# LPmini-Prototype_1_2.net
KiCad netlist of a schematic drawn in EAGLE
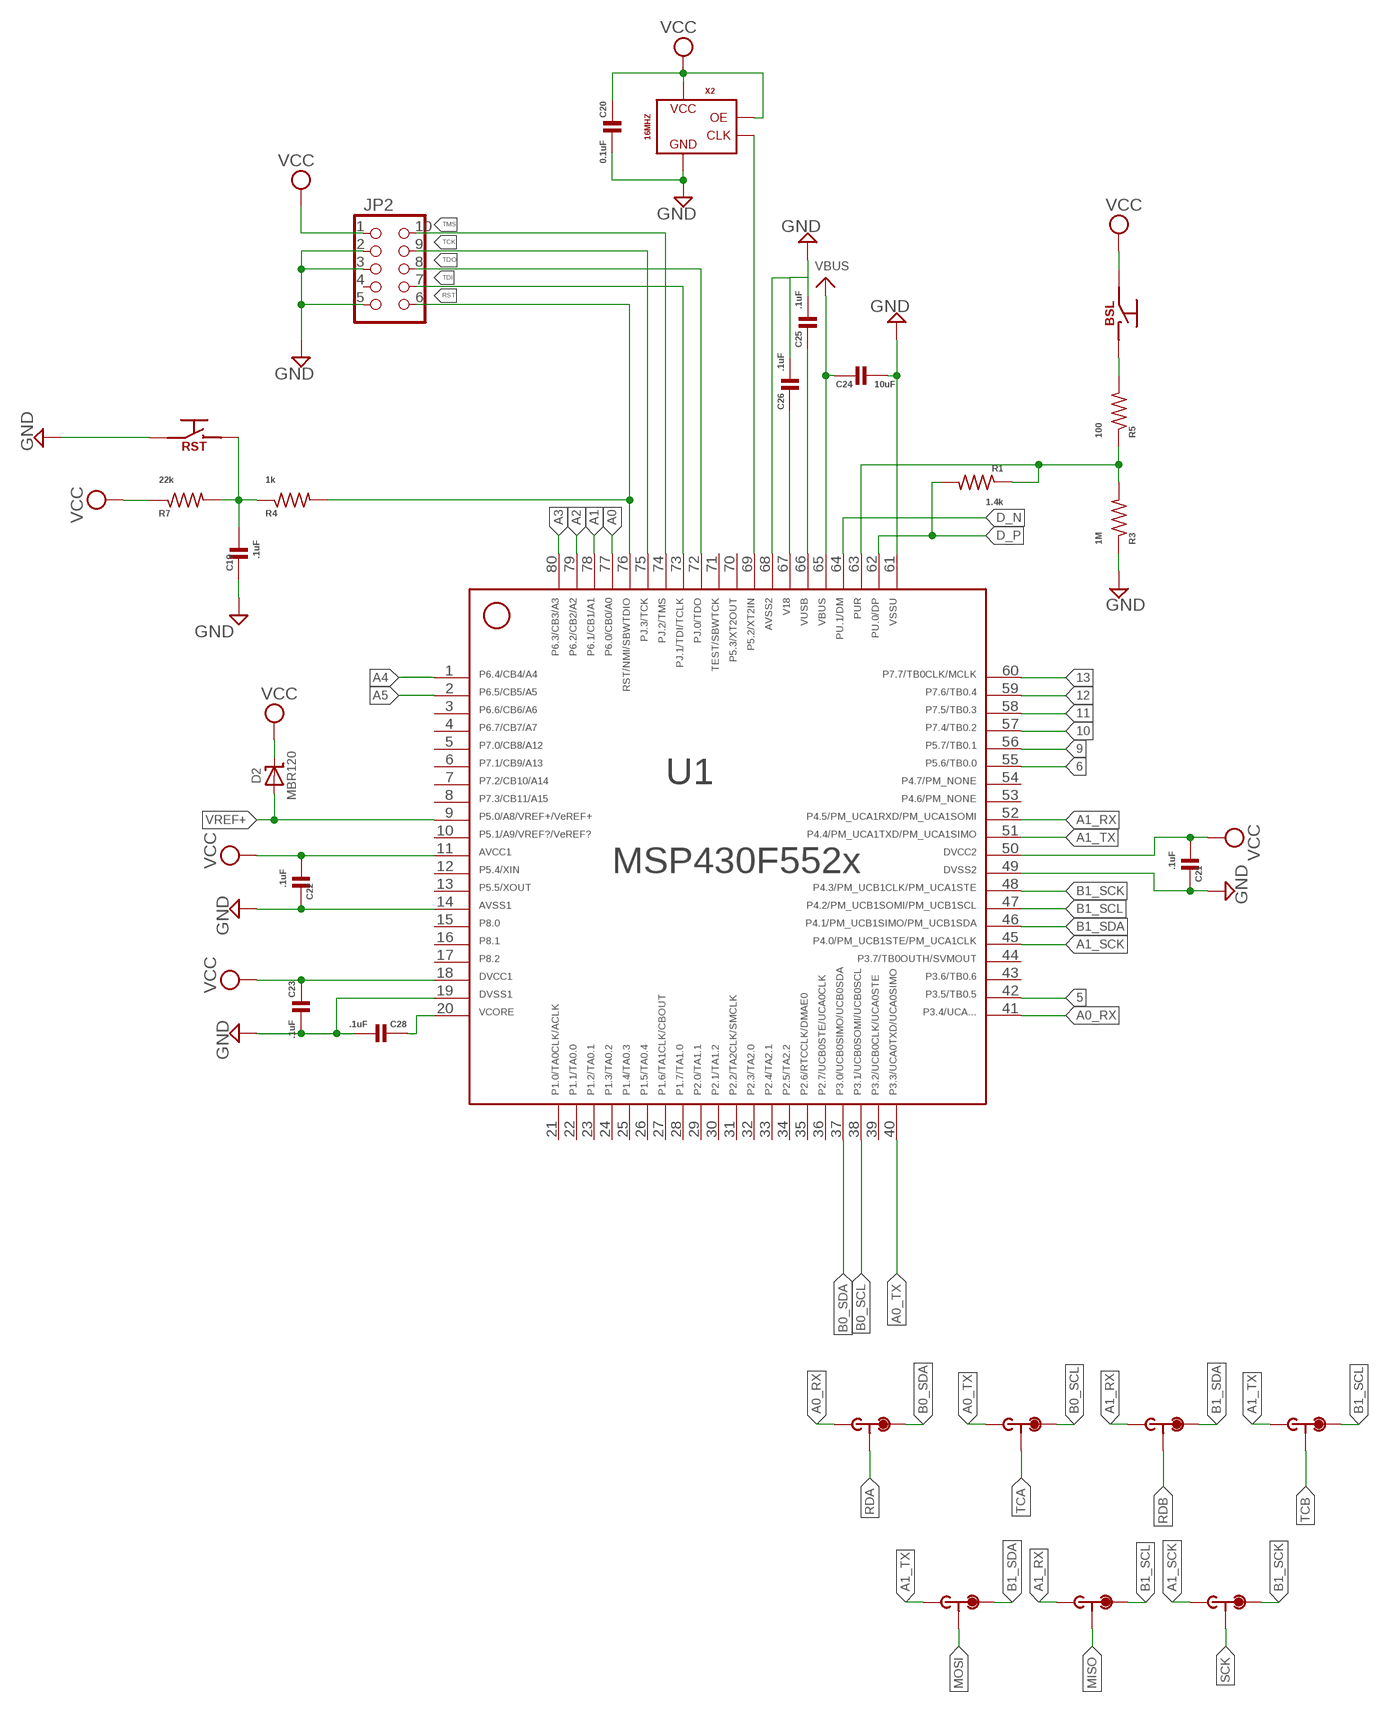
[diagram p0: schematic, sheet 1, part 1 of 2]
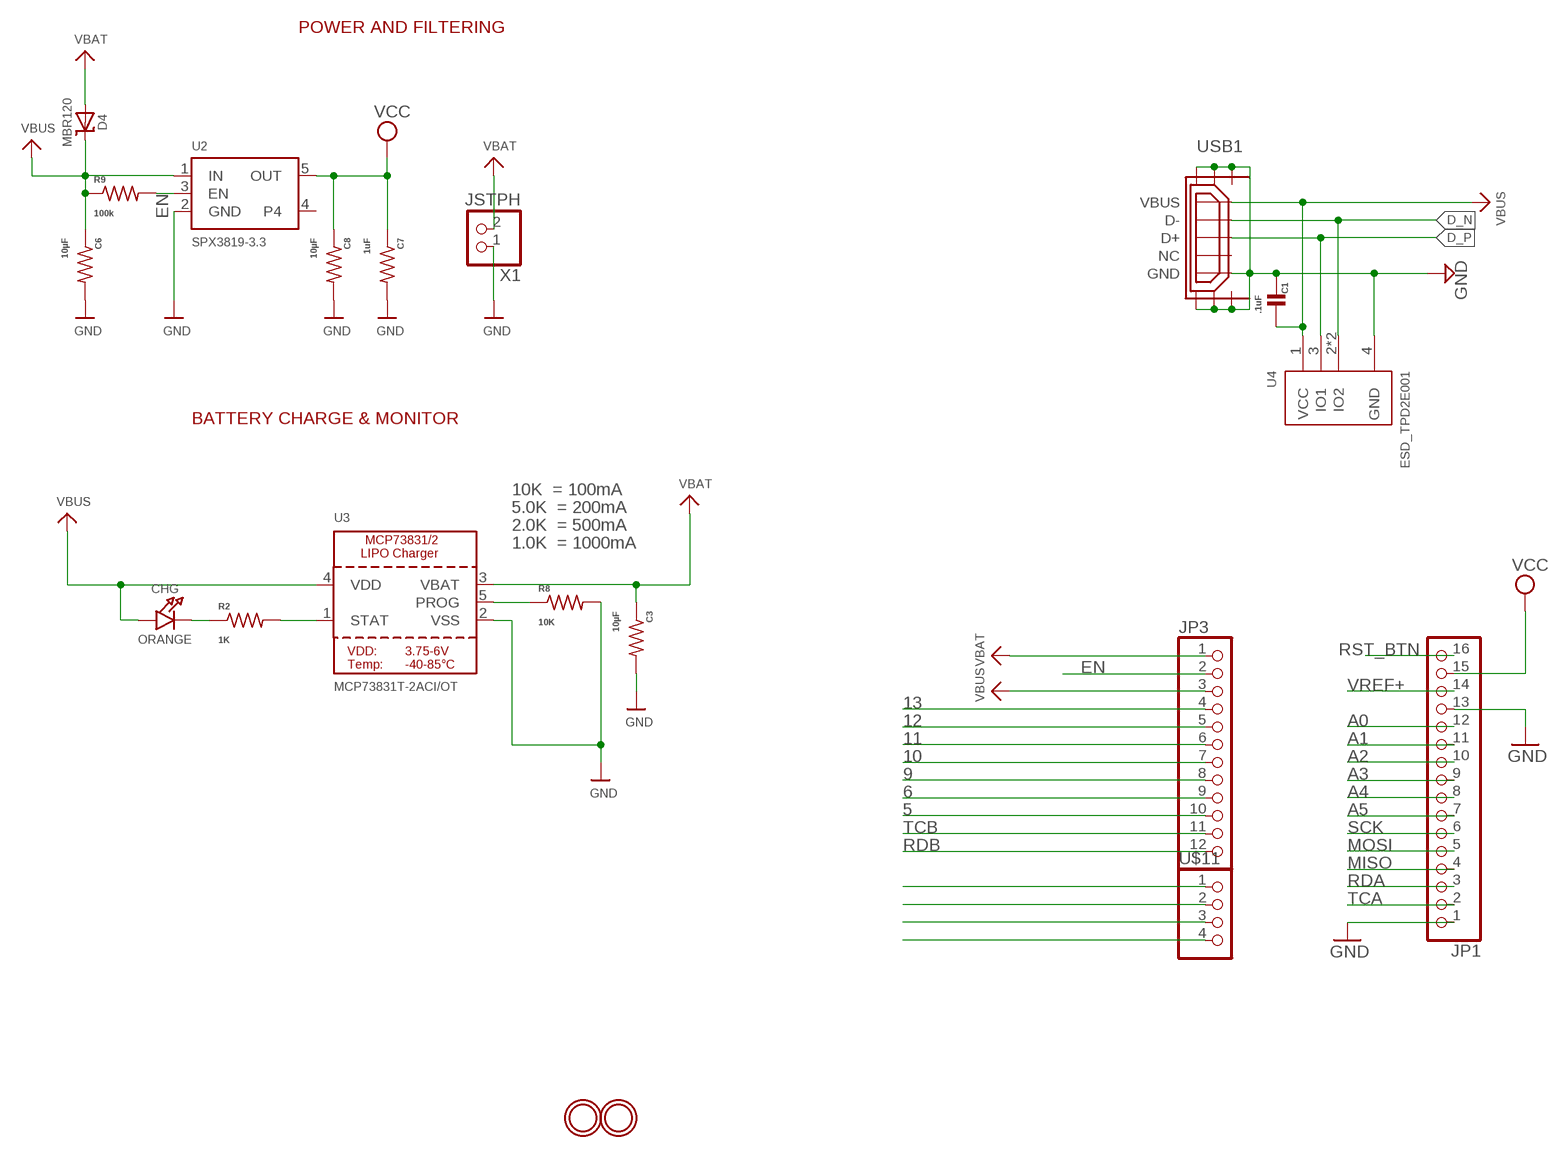
[diagram p1: schematic, sheet 1, part 2 of 2]

(export (version "E")
  (design (tool "Eeschema 10.0.6"))
  (components
    (comp (ref "BSL")
      (value "PB_SMALL_SMD")
      (footprint "eagle-import:PB_KMR2")
      (libsource (lib "eagle-import") (part "PB_SMALL_SMD"))
    )
    (comp (ref "C1")
      (value ".1uF")
      (footprint "eagle-import:C0402")
      (libsource (lib "eagle-import") (part "C-EUC0402"))
    )
    (comp (ref "C3")
      (value "10µF")
      (footprint "eagle-import:R0603")
      (libsource (lib "eagle-import") (part "R-US_R0603"))
    )
    (comp (ref "C6")
      (value "10µF")
      (footprint "eagle-import:R0603")
      (libsource (lib "eagle-import") (part "R-US_R0603"))
    )
    (comp (ref "C7")
      (value "1uF")
      (footprint "eagle-import:R0402")
      (libsource (lib "eagle-import") (part "R-US_R0402"))
    )
    (comp (ref "C8")
      (value "10µF")
      (footprint "eagle-import:R0603")
      (libsource (lib "eagle-import") (part "R-US_R0603"))
    )
    (comp (ref "C19")
      (value ".1uF")
      (footprint "eagle-import:C0402")
      (libsource (lib "eagle-import") (part "C-EUC0402"))
    )
    (comp (ref "C20")
      (value "0.1uF")
      (footprint "eagle-import:C0402")
      (libsource (lib "eagle-import") (part "C-EUC0402"))
    )
    (comp (ref "C21")
      (value ".1uF")
      (footprint "eagle-import:C0402")
      (libsource (lib "eagle-import") (part "C-EUC0402"))
    )
    (comp (ref "C22")
      (value ".1uF")
      (footprint "eagle-import:C0402")
      (libsource (lib "eagle-import") (part "C-EUC0402"))
    )
    (comp (ref "C23")
      (value ".1uF")
      (footprint "eagle-import:C0402")
      (libsource (lib "eagle-import") (part "C-EUC0402"))
    )
    (comp (ref "C24")
      (value "10uF")
      (footprint "eagle-import:C0603")
      (libsource (lib "eagle-import") (part "C-EUC0603"))
    )
    (comp (ref "C25")
      (value ".1uF")
      (footprint "eagle-import:C0402")
      (libsource (lib "eagle-import") (part "C-EUC0402"))
    )
    (comp (ref "C26")
      (value ".1uF")
      (footprint "eagle-import:C0402")
      (libsource (lib "eagle-import") (part "C-EUC0402"))
    )
    (comp (ref "C28")
      (value ".1uF")
      (footprint "eagle-import:C0402")
      (libsource (lib "eagle-import") (part "C-EUC0402"))
    )
    (comp (ref "CHG")
      (value "ORANGE")
      (footprint "eagle-import:CHIPLED_0805_NOOUTLINE")
      (libsource (lib "eagle-import") (part "LED0805_NOOUTLINE"))
    )
    (comp (ref "D2")
      (value "MBR120")
      (footprint "eagle-import:SOD-123")
      (libsource (lib "eagle-import") (part "DIODE-SCHOTTKYSOD-123"))
    )
    (comp (ref "D4")
      (value "MBR120")
      (footprint "eagle-import:SOD-123")
      (libsource (lib "eagle-import") (part "DIODE-SCHOTTKYSOD-123"))
    )
    (comp (ref "JP1")
      (value "HEADER-1X16ROUND")
      (footprint "eagle-import:1X16_ROUND")
      (libsource (lib "eagle-import") (part "HEADER-1X16ROUND"))
    )
    (comp (ref "JP2")
      (value "PINHD_2X05SMD")
      (footprint "eagle-import:2X05-SMALL_SMD")
      (libsource (lib "eagle-import") (part "PINHD_2X05SMD"))
    )
    (comp (ref "JP3")
      (value "HEADER-1X12")
      (footprint "eagle-import:1X12_ROUND")
      (libsource (lib "eagle-import") (part "HEADER-1X12"))
    )
    (comp (ref "R1")
      (value "1.4k")
      (footprint "eagle-import:R0402")
      (libsource (lib "eagle-import") (part "R-US_R0402"))
    )
    (comp (ref "R2")
      (value "1K")
      (footprint "eagle-import:R0402")
      (libsource (lib "eagle-import") (part "R-US_R0402"))
    )
    (comp (ref "R3")
      (value "1M")
      (footprint "eagle-import:R0402")
      (libsource (lib "eagle-import") (part "R-US_R0402"))
    )
    (comp (ref "R4")
      (value "1k")
      (footprint "eagle-import:R0402")
      (libsource (lib "eagle-import") (part "R-US_R0402"))
    )
    (comp (ref "R5")
      (value "100")
      (footprint "eagle-import:R0402")
      (libsource (lib "eagle-import") (part "R-US_R0402"))
    )
    (comp (ref "R7")
      (value "22k")
      (footprint "eagle-import:R0402")
      (libsource (lib "eagle-import") (part "R-US_R0402"))
    )
    (comp (ref "R8")
      (value "10K")
      (footprint "eagle-import:R0402")
      (libsource (lib "eagle-import") (part "R-US_R0402"))
    )
    (comp (ref "R9")
      (value "100k")
      (footprint "eagle-import:R0402")
      (libsource (lib "eagle-import") (part "R-US_R0402"))
    )
    (comp (ref "RST")
      (value "PB_SMALL_SMD")
      (footprint "eagle-import:PB_KMR2")
      (libsource (lib "eagle-import") (part "PB_SMALL_SMD"))
    )
    (comp (ref "U$2")
      (value "3PT_SOLDER_JUMPER")
      (footprint "eagle-import:SOLDER_JUMPER_3")
      (libsource (lib "eagle-import") (part "3PT_SOLDER_JUMPER"))
    )
    (comp (ref "U$4")
      (value "3PT_SOLDER_JUMPER")
      (footprint "eagle-import:SOLDER_JUMPER_3")
      (libsource (lib "eagle-import") (part "3PT_SOLDER_JUMPER"))
    )
    (comp (ref "U$5")
      (value "3PT_SOLDER_JUMPER")
      (footprint "eagle-import:SOLDER_JUMPER_3")
      (libsource (lib "eagle-import") (part "3PT_SOLDER_JUMPER"))
    )
    (comp (ref "U$6")
      (value "3PT_SOLDER_JUMPER")
      (footprint "eagle-import:SOLDER_JUMPER_3")
      (libsource (lib "eagle-import") (part "3PT_SOLDER_JUMPER"))
    )
    (comp (ref "U$8")
      (value "3PT_SOLDER_JUMPER")
      (footprint "eagle-import:SOLDER_JUMPER_3")
      (libsource (lib "eagle-import") (part "3PT_SOLDER_JUMPER"))
    )
    (comp (ref "U$9")
      (value "3PT_SOLDER_JUMPER")
      (footprint "eagle-import:SOLDER_JUMPER_3")
      (libsource (lib "eagle-import") (part "3PT_SOLDER_JUMPER"))
    )
    (comp (ref "U$10")
      (value "3PT_SOLDER_JUMPER")
      (footprint "eagle-import:SOLDER_JUMPER_3")
      (libsource (lib "eagle-import") (part "3PT_SOLDER_JUMPER"))
    )
    (comp (ref "U$11")
      (value "PINHD_1X4")
      (footprint "eagle-import:1X04")
      (libsource (lib "eagle-import") (part "PINHD_1X4"))
    )
    (comp (ref "U$31")
      (value "MOUNTINGHOLE2.5")
      (footprint "eagle-import:MOUNTINGHOLE_2.5_PLATED")
      (libsource (lib "eagle-import") (part "MOUNTINGHOLE2.5"))
    )
    (comp (ref "U$32")
      (value "MOUNTINGHOLE2.5")
      (footprint "eagle-import:MOUNTINGHOLE_2.5_PLATED")
      (libsource (lib "eagle-import") (part "MOUNTINGHOLE2.5"))
    )
    (comp (ref "U1")
      (value "TI_MSP430_V16_INTERN_F552X---PN80")
      (footprint "eagle-import:TI_MSP430_V16_INTERN_PN80")
      (libsource (lib "eagle-import") (part "TI_MSP430_V16_INTERN_F552X---PN80"))
    )
    (comp (ref "U2")
      (value "SPX3819-3.3")
      (footprint "eagle-import:SOT23-5")
      (libsource (lib "eagle-import") (part "VREG_SOT23-5"))
    )
    (comp (ref "U3")
      (value "MCP73831T-2ACI/OT")
      (footprint "eagle-import:SOT23-5")
      (libsource (lib "eagle-import") (part "MCP73831/2"))
    )
    (comp (ref "U4")
      (value "ESD_TPD2E001")
      (footprint "eagle-import:PROJECT7264_TPD2E001-DRL")
      (libsource (lib "eagle-import") (part "ESD_TPD2E001"))
    )
    (comp (ref "USB1")
      (value "USB_CON-UPDATE_USB_MICRO_FLIPPED")
      (footprint "eagle-import:USB_CON-UPDATE_HIROSE-ZX62R-B-5P")
      (libsource (lib "eagle-import") (part "USB_CON-UPDATE_USB_MICRO_FLIPPED"))
    )
    (comp (ref "X1")
      (value "JSTPH")
      (footprint "eagle-import:JSTPH2")
      (libsource (lib "eagle-import") (part "CON_JST_PH_2PIN"))
    )
    (comp (ref "X2")
      (value "16MHZ")
      (footprint "eagle-import:OSCILLATOR_3.3X2.6")
      (libsource (lib "eagle-import") (part "OSCILLATOR_SMDHC335R"))
    )
  )
  (nets
    (net (code "1") (name "/EN") (class "Default")
      (node (ref "JP3") (pin "2") (pinfunction "2_2") (pintype "passive"))
      (node (ref "R9") (pin "2") (pinfunction "2_2") (pintype "passive"))
      (node (ref "U2") (pin "3") (pinfunction "EN_3") (pintype "input"))
    )
    (net (code "2") (name "/RST_BTN") (class "Default")
      (node (ref "C19") (pin "1") (pinfunction "1_1") (pintype "passive"))
      (node (ref "JP1") (pin "16") (pinfunction "16_16") (pintype "passive"))
      (node (ref "R4") (pin "1") (pinfunction "1_1") (pintype "passive"))
      (node (ref "R7") (pin "2") (pinfunction "2_2") (pintype "passive"))
      (node (ref "RST") (pin "2A") (pinfunction "B_2A") (pintype "bidirectional"))
      (node (ref "RST") (pin "2B") (pinfunction "B_2B") (pintype "bidirectional"))
    )
    (net (code "3") (name "5") (class "Default")
      (node (ref "JP3") (pin "10") (pinfunction "10_10") (pintype "passive"))
      (node (ref "U1") (pin "42") (pinfunction "42_42") (pintype "bidirectional"))
    )
    (net (code "4") (name "6") (class "Default")
      (node (ref "JP3") (pin "9") (pinfunction "9_9") (pintype "passive"))
      (node (ref "U1") (pin "55") (pinfunction "55_55") (pintype "bidirectional"))
    )
    (net (code "5") (name "9") (class "Default")
      (node (ref "JP3") (pin "8") (pinfunction "8_8") (pintype "passive"))
      (node (ref "U1") (pin "56") (pinfunction "56_56") (pintype "bidirectional"))
    )
    (net (code "6") (name "10") (class "Default")
      (node (ref "JP3") (pin "7") (pinfunction "7_7") (pintype "passive"))
      (node (ref "U1") (pin "57") (pinfunction "57_57") (pintype "bidirectional"))
    )
    (net (code "7") (name "11") (class "Default")
      (node (ref "JP3") (pin "6") (pinfunction "6_6") (pintype "passive"))
      (node (ref "U1") (pin "58") (pinfunction "58_58") (pintype "bidirectional"))
    )
    (net (code "8") (name "12") (class "Default")
      (node (ref "JP3") (pin "5") (pinfunction "5_5") (pintype "passive"))
      (node (ref "U1") (pin "59") (pinfunction "59_59") (pintype "bidirectional"))
    )
    (net (code "9") (name "13") (class "Default")
      (node (ref "JP3") (pin "4") (pinfunction "4_4") (pintype "passive"))
      (node (ref "U1") (pin "60") (pinfunction "60_60") (pintype "bidirectional"))
    )
    (net (code "10") (name "A0") (class "Default")
      (node (ref "JP1") (pin "12") (pinfunction "12_12") (pintype "passive"))
      (node (ref "U1") (pin "77") (pinfunction "77_77") (pintype "bidirectional"))
    )
    (net (code "11") (name "A0_RX") (class "Default")
      (node (ref "U$2") (pin "2") (pinfunction "NO_2") (pintype "bidirectional"))
      (node (ref "U1") (pin "41") (pinfunction "41_41") (pintype "bidirectional"))
    )
    (net (code "12") (name "A0_TX") (class "Default")
      (node (ref "U$8") (pin "2") (pinfunction "NO_2") (pintype "bidirectional"))
      (node (ref "U1") (pin "40") (pinfunction "40_40") (pintype "bidirectional"))
    )
    (net (code "13") (name "A1") (class "Default")
      (node (ref "JP1") (pin "11") (pinfunction "11_11") (pintype "passive"))
      (node (ref "U1") (pin "78") (pinfunction "78_78") (pintype "bidirectional"))
    )
    (net (code "14") (name "A1_RX") (class "Default")
      (node (ref "U$5") (pin "2") (pinfunction "NO_2") (pintype "bidirectional"))
      (node (ref "U$9") (pin "2") (pinfunction "NO_2") (pintype "bidirectional"))
      (node (ref "U1") (pin "52") (pinfunction "52_52") (pintype "bidirectional"))
    )
    (net (code "15") (name "A1_SCK") (class "Default")
      (node (ref "U$6") (pin "2") (pinfunction "NO_2") (pintype "bidirectional"))
      (node (ref "U1") (pin "45") (pinfunction "45_45") (pintype "bidirectional"))
    )
    (net (code "16") (name "A1_TX") (class "Default")
      (node (ref "U$10") (pin "2") (pinfunction "NO_2") (pintype "bidirectional"))
      (node (ref "U$4") (pin "2") (pinfunction "NO_2") (pintype "bidirectional"))
      (node (ref "U1") (pin "51") (pinfunction "51_51") (pintype "bidirectional"))
    )
    (net (code "17") (name "A2") (class "Default")
      (node (ref "JP1") (pin "10") (pinfunction "10_10") (pintype "passive"))
      (node (ref "U1") (pin "79") (pinfunction "79_79") (pintype "bidirectional"))
    )
    (net (code "18") (name "A3") (class "Default")
      (node (ref "JP1") (pin "9") (pinfunction "9_9") (pintype "passive"))
      (node (ref "U1") (pin "80") (pinfunction "80_80") (pintype "bidirectional"))
    )
    (net (code "19") (name "A4") (class "Default")
      (node (ref "JP1") (pin "8") (pinfunction "8_8") (pintype "passive"))
      (node (ref "U1") (pin "1") (pinfunction "1_1") (pintype "bidirectional"))
    )
    (net (code "20") (name "A5") (class "Default")
      (node (ref "JP1") (pin "7") (pinfunction "7_7") (pintype "passive"))
      (node (ref "U1") (pin "2") (pinfunction "2_2") (pintype "bidirectional"))
    )
    (net (code "21") (name "B0_SCL") (class "Default")
      (node (ref "U$8") (pin "1") (pinfunction "NC_1") (pintype "bidirectional"))
      (node (ref "U1") (pin "38") (pinfunction "38_38") (pintype "bidirectional"))
    )
    (net (code "22") (name "B0_SDA") (class "Default")
      (node (ref "U$2") (pin "1") (pinfunction "NC_1") (pintype "bidirectional"))
      (node (ref "U1") (pin "37") (pinfunction "37_37") (pintype "bidirectional"))
    )
    (net (code "23") (name "B1_SCK") (class "Default")
      (node (ref "U$6") (pin "1") (pinfunction "NC_1") (pintype "bidirectional"))
      (node (ref "U1") (pin "48") (pinfunction "48_48") (pintype "bidirectional"))
    )
    (net (code "24") (name "B1_SCL") (class "Default")
      (node (ref "U$10") (pin "1") (pinfunction "NC_1") (pintype "bidirectional"))
      (node (ref "U$5") (pin "1") (pinfunction "NC_1") (pintype "bidirectional"))
      (node (ref "U1") (pin "47") (pinfunction "47_47") (pintype "bidirectional"))
    )
    (net (code "25") (name "B1_SDA") (class "Default")
      (node (ref "U$4") (pin "1") (pinfunction "NC_1") (pintype "bidirectional"))
      (node (ref "U$9") (pin "1") (pinfunction "NC_1") (pintype "bidirectional"))
      (node (ref "U1") (pin "46") (pinfunction "46_46") (pintype "bidirectional"))
    )
    (net (code "26") (name "D_N") (class "Default")
      (node (ref "U1") (pin "64") (pinfunction "64_64") (pintype "bidirectional"))
      (node (ref "U4") (pin "2") (pinfunction "IO2_2") (pintype "bidirectional"))
      (node (ref "U4") (pin "5") (pinfunction "IO2_5") (pintype "bidirectional"))
      (node (ref "USB1") (pin "D-") (pinfunction "D-_D-") (pintype "input"))
    )
    (net (code "27") (name "D_P") (class "Default")
      (node (ref "R1") (pin "2") (pinfunction "2_2") (pintype "passive"))
      (node (ref "U1") (pin "62") (pinfunction "62_62") (pintype "bidirectional"))
      (node (ref "U4") (pin "3") (pinfunction "IO1_3") (pintype "bidirectional"))
      (node (ref "USB1") (pin "D+") (pinfunction "D+_D+") (pintype "input"))
    )
    (net (code "28") (name "GND") (class "Default")
      (node (ref "C1") (pin "2") (pinfunction "2_2") (pintype "passive"))
      (node (ref "C19") (pin "2") (pinfunction "2_2") (pintype "passive"))
      (node (ref "C20") (pin "2") (pinfunction "2_2") (pintype "passive"))
      (node (ref "C21") (pin "2") (pinfunction "2_2") (pintype "passive"))
      (node (ref "C22") (pin "2") (pinfunction "2_2") (pintype "passive"))
      (node (ref "C23") (pin "2") (pinfunction "2_2") (pintype "passive"))
      (node (ref "C24") (pin "2") (pinfunction "2_2") (pintype "passive"))
      (node (ref "C25") (pin "2") (pinfunction "2_2") (pintype "passive"))
      (node (ref "C26") (pin "2") (pinfunction "2_2") (pintype "passive"))
      (node (ref "C28") (pin "2") (pinfunction "2_2") (pintype "passive"))
      (node (ref "C3") (pin "2") (pinfunction "2_2") (pintype "passive"))
      (node (ref "C6") (pin "2") (pinfunction "2_2") (pintype "passive"))
      (node (ref "C7") (pin "2") (pinfunction "2_2") (pintype "passive"))
      (node (ref "C8") (pin "2") (pinfunction "2_2") (pintype "passive"))
      (node (ref "JP1") (pin "1") (pinfunction "1_1") (pintype "passive"))
      (node (ref "JP1") (pin "13") (pinfunction "13_13") (pintype "passive"))
      (node (ref "JP2") (pin "2") (pinfunction "2_2") (pintype "passive"))
      (node (ref "JP2") (pin "3") (pinfunction "3_3") (pintype "passive"))
      (node (ref "JP2") (pin "5") (pinfunction "5_5") (pintype "passive"))
      (node (ref "R3") (pin "1") (pinfunction "1_1") (pintype "passive"))
      (node (ref "R8") (pin "2") (pinfunction "2_2") (pintype "passive"))
      (node (ref "RST") (pin "1A") (pinfunction "A_1A") (pintype "bidirectional"))
      (node (ref "RST") (pin "1B") (pinfunction "A_1B") (pintype "bidirectional"))
      (node (ref "U1") (pin "14") (pinfunction "14_14") (pintype "power_in"))
      (node (ref "U1") (pin "19") (pinfunction "19_19") (pintype "power_in"))
      (node (ref "U1") (pin "49") (pinfunction "49_49") (pintype "power_in"))
      (node (ref "U1") (pin "61") (pinfunction "61_61") (pintype "power_in"))
      (node (ref "U1") (pin "68") (pinfunction "68_68") (pintype "power_in"))
      (node (ref "U2") (pin "2") (pinfunction "GND_2") (pintype "power_in"))
      (node (ref "U3") (pin "2") (pinfunction "VSS_2") (pintype "power_in"))
      (node (ref "U4") (pin "4") (pinfunction "GND_4") (pintype "power_in"))
      (node (ref "USB1") (pin "GND") (pinfunction "GND_GND") (pintype "input"))
      (node (ref "USB1") (pin "SHIELD1") (pinfunction "SHIELD1_SHIELD1") (pintype "bidirectional"))
      (node (ref "USB1") (pin "SHIELD2") (pinfunction "SHIELD2_SHIELD2") (pintype "bidirectional"))
      (node (ref "USB1") (pin "SHIELD3") (pinfunction "SHIELD3_SHIELD3") (pintype "bidirectional"))
      (node (ref "USB1") (pin "SHIELD4") (pinfunction "SHIELD4_SHIELD4") (pintype "bidirectional"))
      (node (ref "USB1") (pin "SHIELD5") (pinfunction "SHIELD5_SHIELD5") (pintype "bidirectional"))
      (node (ref "USB1") (pin "SHIELD6") (pinfunction "SHIELD6_SHIELD6") (pintype "bidirectional"))
      (node (ref "X1") (pin "1") (pinfunction "1_1") (pintype "passive"))
      (node (ref "X2") (pin "2") (pinfunction "2_2") (pintype "bidirectional"))
    )
    (net (code "29") (name "MISO") (class "Default")
      (node (ref "JP1") (pin "4") (pinfunction "4_4") (pintype "passive"))
      (node (ref "U$5") (pin "C") (pinfunction "IN_C") (pintype "bidirectional"))
    )
    (net (code "30") (name "MOSI") (class "Default")
      (node (ref "JP1") (pin "5") (pinfunction "5_5") (pintype "passive"))
      (node (ref "U$4") (pin "C") (pinfunction "IN_C") (pintype "bidirectional"))
    )
    (net (code "31") (name "Net-(BSL-B-Pad2A)") (class "Default")
      (node (ref "BSL") (pin "2A") (pinfunction "B_2A") (pintype "bidirectional"))
      (node (ref "BSL") (pin "2B") (pinfunction "B_2B") (pintype "bidirectional"))
      (node (ref "R5") (pin "2") (pinfunction "2_2") (pintype "passive"))
    )
    (net (code "32") (name "Net-(C25-Pad1)") (class "Default")
      (node (ref "C25") (pin "1") (pinfunction "1_1") (pintype "passive"))
      (node (ref "U1") (pin "66") (pinfunction "66_66") (pintype "power_in"))
    )
    (net (code "33") (name "Net-(C26-Pad1)") (class "Default")
      (node (ref "C26") (pin "1") (pinfunction "1_1") (pintype "passive"))
      (node (ref "U1") (pin "67") (pinfunction "67_67") (pintype "power_in"))
    )
    (net (code "34") (name "Net-(C28-Pad1)") (class "Default")
      (node (ref "C28") (pin "1") (pinfunction "1_1") (pintype "passive"))
      (node (ref "U1") (pin "20") (pinfunction "20_20") (pintype "power_in"))
    )
    (net (code "35") (name "Net-(CHG-PadC)") (class "Default")
      (node (ref "CHG") (pin "C") (pinfunction "C_C") (pintype "passive"))
      (node (ref "R2") (pin "1") (pinfunction "1_1") (pintype "passive"))
    )
    (net (code "36") (name "Net-(R1-Pad1)") (class "Default")
      (node (ref "R1") (pin "1") (pinfunction "1_1") (pintype "passive"))
      (node (ref "R3") (pin "2") (pinfunction "2_2") (pintype "passive"))
      (node (ref "R5") (pin "1") (pinfunction "1_1") (pintype "passive"))
      (node (ref "U1") (pin "63") (pinfunction "63_63") (pintype "bidirectional"))
    )
    (net (code "37") (name "Net-(U1-Pad69)") (class "Default")
      (node (ref "U1") (pin "69") (pinfunction "69_69") (pintype "bidirectional"))
      (node (ref "X2") (pin "3") (pinfunction "3_3") (pintype "bidirectional"))
    )
    (net (code "38") (name "Net-(U3-PROG)") (class "Default")
      (node (ref "R8") (pin "1") (pinfunction "1_1") (pintype "passive"))
      (node (ref "U3") (pin "5") (pinfunction "PROG_5") (pintype "input"))
    )
    (net (code "39") (name "Net-(U3-STAT)") (class "Default")
      (node (ref "R2") (pin "2") (pinfunction "2_2") (pintype "passive"))
      (node (ref "U3") (pin "1") (pinfunction "STAT_1") (pintype "output"))
    )
    (net (code "40") (name "RDA") (class "Default")
      (node (ref "JP1") (pin "3") (pinfunction "3_3") (pintype "passive"))
      (node (ref "U$2") (pin "C") (pinfunction "IN_C") (pintype "bidirectional"))
    )
    (net (code "41") (name "RDB") (class "Default")
      (node (ref "JP3") (pin "12") (pinfunction "12_12") (pintype "passive"))
      (node (ref "U$9") (pin "C") (pinfunction "IN_C") (pintype "bidirectional"))
    )
    (net (code "42") (name "RST") (class "Default")
      (node (ref "JP2") (pin "6") (pinfunction "6_6") (pintype "passive"))
      (node (ref "R4") (pin "2") (pinfunction "2_2") (pintype "passive"))
      (node (ref "U1") (pin "76") (pinfunction "76_76") (pintype "bidirectional"))
    )
    (net (code "43") (name "SCK") (class "Default")
      (node (ref "JP1") (pin "6") (pinfunction "6_6") (pintype "passive"))
      (node (ref "U$6") (pin "C") (pinfunction "IN_C") (pintype "bidirectional"))
    )
    (net (code "44") (name "TCA") (class "Default")
      (node (ref "JP1") (pin "2") (pinfunction "2_2") (pintype "passive"))
      (node (ref "U$8") (pin "C") (pinfunction "IN_C") (pintype "bidirectional"))
    )
    (net (code "45") (name "TCB") (class "Default")
      (node (ref "JP3") (pin "11") (pinfunction "11_11") (pintype "passive"))
      (node (ref "U$10") (pin "C") (pinfunction "IN_C") (pintype "bidirectional"))
    )
    (net (code "46") (name "TCK") (class "Default")
      (node (ref "JP2") (pin "9") (pinfunction "9_9") (pintype "passive"))
      (node (ref "U1") (pin "75") (pinfunction "75_75") (pintype "bidirectional"))
    )
    (net (code "47") (name "TDI") (class "Default")
      (node (ref "JP2") (pin "7") (pinfunction "7_7") (pintype "passive"))
      (node (ref "U1") (pin "73") (pinfunction "73_73") (pintype "bidirectional"))
    )
    (net (code "48") (name "TDO") (class "Default")
      (node (ref "JP2") (pin "8") (pinfunction "8_8") (pintype "passive"))
      (node (ref "U1") (pin "72") (pinfunction "72_72") (pintype "bidirectional"))
    )
    (net (code "49") (name "TMS") (class "Default")
      (node (ref "JP2") (pin "10") (pinfunction "10_10") (pintype "passive"))
      (node (ref "U1") (pin "74") (pinfunction "74_74") (pintype "bidirectional"))
    )
    (net (code "50") (name "VBAT") (class "Default")
      (node (ref "C3") (pin "1") (pinfunction "1_1") (pintype "passive"))
      (node (ref "D4") (pin "A") (pinfunction "A_A") (pintype "passive"))
      (node (ref "JP3") (pin "1") (pinfunction "1_1") (pintype "passive"))
      (node (ref "U3") (pin "3") (pinfunction "VBAT_3") (pintype "power_in"))
      (node (ref "X1") (pin "2") (pinfunction "2_2") (pintype "passive"))
    )
    (net (code "51") (name "VBUS") (class "Default")
      (node (ref "C1") (pin "1") (pinfunction "1_1") (pintype "passive"))
      (node (ref "C24") (pin "1") (pinfunction "1_1") (pintype "passive"))
      (node (ref "C6") (pin "1") (pinfunction "1_1") (pintype "passive"))
      (node (ref "CHG") (pin "A") (pinfunction "A_A") (pintype "passive"))
      (node (ref "D4") (pin "C") (pinfunction "C_C") (pintype "passive"))
      (node (ref "JP3") (pin "3") (pinfunction "3_3") (pintype "passive"))
      (node (ref "R9") (pin "1") (pinfunction "1_1") (pintype "passive"))
      (node (ref "U1") (pin "65") (pinfunction "65_65") (pintype "power_in"))
      (node (ref "U2") (pin "1") (pinfunction "IN_1") (pintype "power_in"))
      (node (ref "U3") (pin "4") (pinfunction "VDD_4") (pintype "power_in"))
      (node (ref "U4") (pin "1") (pinfunction "VCC_1") (pintype "power_in"))
      (node (ref "USB1") (pin "VBUS") (pinfunction "VBUS_VBUS") (pintype "input"))
    )
    (net (code "52") (name "VCC") (class "Default")
      (node (ref "BSL") (pin "1A") (pinfunction "A_1A") (pintype "bidirectional"))
      (node (ref "BSL") (pin "1B") (pinfunction "A_1B") (pintype "bidirectional"))
      (node (ref "C20") (pin "1") (pinfunction "1_1") (pintype "passive"))
      (node (ref "C21") (pin "1") (pinfunction "1_1") (pintype "passive"))
      (node (ref "C22") (pin "1") (pinfunction "1_1") (pintype "passive"))
      (node (ref "C23") (pin "1") (pinfunction "1_1") (pintype "passive"))
      (node (ref "C7") (pin "1") (pinfunction "1_1") (pintype "passive"))
      (node (ref "C8") (pin "1") (pinfunction "1_1") (pintype "passive"))
      (node (ref "D2") (pin "C") (pinfunction "C_C") (pintype "passive"))
      (node (ref "JP1") (pin "15") (pinfunction "15_15") (pintype "passive"))
      (node (ref "JP2") (pin "1") (pinfunction "1_1") (pintype "passive"))
      (node (ref "R7") (pin "1") (pinfunction "1_1") (pintype "passive"))
      (node (ref "U1") (pin "11") (pinfunction "11_11") (pintype "power_in"))
      (node (ref "U1") (pin "18") (pinfunction "18_18") (pintype "power_in"))
      (node (ref "U1") (pin "50") (pinfunction "50_50") (pintype "power_in"))
      (node (ref "U2") (pin "5") (pinfunction "OUT_5") (pintype "power_in"))
      (node (ref "X2") (pin "1") (pinfunction "1_1") (pintype "bidirectional"))
      (node (ref "X2") (pin "4") (pinfunction "4_4") (pintype "bidirectional"))
    )
    (net (code "53") (name "VREF+") (class "Default")
      (node (ref "D2") (pin "A") (pinfunction "A_A") (pintype "passive"))
      (node (ref "JP1") (pin "14") (pinfunction "14_14") (pintype "passive"))
      (node (ref "U1") (pin "9") (pinfunction "9_9") (pintype "bidirectional"))
    )
    (net (code "54") (name "unconnected-(JP2-Pad4)") (class "Default")
      (node (ref "JP2") (pin "4") (pinfunction "4_4") (pintype "passive"))
    )
    (net (code "55") (name "unconnected-(U$11-Pad1)") (class "Default")
      (node (ref "U$11") (pin "1") (pinfunction "1_1") (pintype "passive"))
    )
    (net (code "56") (name "unconnected-(U$11-Pad2)") (class "Default")
      (node (ref "U$11") (pin "2") (pinfunction "2_2") (pintype "passive"))
    )
    (net (code "57") (name "unconnected-(U$11-Pad3)") (class "Default")
      (node (ref "U$11") (pin "3") (pinfunction "3_3") (pintype "passive"))
    )
    (net (code "58") (name "unconnected-(U$11-Pad4)") (class "Default")
      (node (ref "U$11") (pin "4") (pinfunction "4_4") (pintype "passive"))
    )
    (net (code "59") (name "unconnected-(U1-Pad3)") (class "Default")
      (node (ref "U1") (pin "3") (pinfunction "3_3") (pintype "bidirectional"))
    )
    (net (code "60") (name "unconnected-(U1-Pad4)") (class "Default")
      (node (ref "U1") (pin "4") (pinfunction "4_4") (pintype "bidirectional"))
    )
    (net (code "61") (name "unconnected-(U1-Pad5)") (class "Default")
      (node (ref "U1") (pin "5") (pinfunction "5_5") (pintype "bidirectional"))
    )
    (net (code "62") (name "unconnected-(U1-Pad6)") (class "Default")
      (node (ref "U1") (pin "6") (pinfunction "6_6") (pintype "bidirectional"))
    )
    (net (code "63") (name "unconnected-(U1-Pad7)") (class "Default")
      (node (ref "U1") (pin "7") (pinfunction "7_7") (pintype "bidirectional"))
    )
    (net (code "64") (name "unconnected-(U1-Pad8)") (class "Default")
      (node (ref "U1") (pin "8") (pinfunction "8_8") (pintype "bidirectional"))
    )
    (net (code "65") (name "unconnected-(U1-Pad10)") (class "Default")
      (node (ref "U1") (pin "10") (pinfunction "10_10") (pintype "bidirectional"))
    )
    (net (code "66") (name "unconnected-(U1-Pad12)") (class "Default")
      (node (ref "U1") (pin "12") (pinfunction "12_12") (pintype "bidirectional"))
    )
    (net (code "67") (name "unconnected-(U1-Pad13)") (class "Default")
      (node (ref "U1") (pin "13") (pinfunction "13_13") (pintype "bidirectional"))
    )
    (net (code "68") (name "unconnected-(U1-Pad15)") (class "Default")
      (node (ref "U1") (pin "15") (pinfunction "15_15") (pintype "bidirectional"))
    )
    (net (code "69") (name "unconnected-(U1-Pad16)") (class "Default")
      (node (ref "U1") (pin "16") (pinfunction "16_16") (pintype "bidirectional"))
    )
    (net (code "70") (name "unconnected-(U1-Pad17)") (class "Default")
      (node (ref "U1") (pin "17") (pinfunction "17_17") (pintype "bidirectional"))
    )
    (net (code "71") (name "unconnected-(U1-Pad21)") (class "Default")
      (node (ref "U1") (pin "21") (pinfunction "21_21") (pintype "bidirectional"))
    )
    (net (code "72") (name "unconnected-(U1-Pad22)") (class "Default")
      (node (ref "U1") (pin "22") (pinfunction "22_22") (pintype "bidirectional"))
    )
    (net (code "73") (name "unconnected-(U1-Pad23)") (class "Default")
      (node (ref "U1") (pin "23") (pinfunction "23_23") (pintype "bidirectional"))
    )
    (net (code "74") (name "unconnected-(U1-Pad24)") (class "Default")
      (node (ref "U1") (pin "24") (pinfunction "24_24") (pintype "bidirectional"))
    )
    (net (code "75") (name "unconnected-(U1-Pad25)") (class "Default")
      (node (ref "U1") (pin "25") (pinfunction "25_25") (pintype "bidirectional"))
    )
    (net (code "76") (name "unconnected-(U1-Pad26)") (class "Default")
      (node (ref "U1") (pin "26") (pinfunction "26_26") (pintype "bidirectional"))
    )
    (net (code "77") (name "unconnected-(U1-Pad27)") (class "Default")
      (node (ref "U1") (pin "27") (pinfunction "27_27") (pintype "bidirectional"))
    )
    (net (code "78") (name "unconnected-(U1-Pad28)") (class "Default")
      (node (ref "U1") (pin "28") (pinfunction "28_28") (pintype "bidirectional"))
    )
    (net (code "79") (name "unconnected-(U1-Pad29)") (class "Default")
      (node (ref "U1") (pin "29") (pinfunction "29_29") (pintype "bidirectional"))
    )
    (net (code "80") (name "unconnected-(U1-Pad30)") (class "Default")
      (node (ref "U1") (pin "30") (pinfunction "30_30") (pintype "bidirectional"))
    )
    (net (code "81") (name "unconnected-(U1-Pad31)") (class "Default")
      (node (ref "U1") (pin "31") (pinfunction "31_31") (pintype "bidirectional"))
    )
    (net (code "82") (name "unconnected-(U1-Pad32)") (class "Default")
      (node (ref "U1") (pin "32") (pinfunction "32_32") (pintype "bidirectional"))
    )
    (net (code "83") (name "unconnected-(U1-Pad33)") (class "Default")
      (node (ref "U1") (pin "33") (pinfunction "33_33") (pintype "bidirectional"))
    )
    (net (code "84") (name "unconnected-(U1-Pad34)") (class "Default")
      (node (ref "U1") (pin "34") (pinfunction "34_34") (pintype "bidirectional"))
    )
    (net (code "85") (name "unconnected-(U1-Pad35)") (class "Default")
      (node (ref "U1") (pin "35") (pinfunction "35_35") (pintype "bidirectional"))
    )
    (net (code "86") (name "unconnected-(U1-Pad36)") (class "Default")
      (node (ref "U1") (pin "36") (pinfunction "36_36") (pintype "bidirectional"))
    )
    (net (code "87") (name "unconnected-(U1-Pad39)") (class "Default")
      (node (ref "U1") (pin "39") (pinfunction "39_39") (pintype "bidirectional"))
    )
    (net (code "88") (name "unconnected-(U1-Pad43)") (class "Default")
      (node (ref "U1") (pin "43") (pinfunction "43_43") (pintype "bidirectional"))
    )
    (net (code "89") (name "unconnected-(U1-Pad44)") (class "Default")
      (node (ref "U1") (pin "44") (pinfunction "44_44") (pintype "bidirectional"))
    )
    (net (code "90") (name "unconnected-(U1-Pad53)") (class "Default")
      (node (ref "U1") (pin "53") (pinfunction "53_53") (pintype "bidirectional"))
    )
    (net (code "91") (name "unconnected-(U1-Pad54)") (class "Default")
      (node (ref "U1") (pin "54") (pinfunction "54_54") (pintype "bidirectional"))
    )
    (net (code "92") (name "unconnected-(U1-Pad70)") (class "Default")
      (node (ref "U1") (pin "70") (pinfunction "70_70") (pintype "bidirectional"))
    )
    (net (code "93") (name "unconnected-(U1-Pad71)") (class "Default")
      (node (ref "U1") (pin "71") (pinfunction "71_71") (pintype "input"))
    )
    (net (code "94") (name "unconnected-(U2-P4-Pad4)") (class "Default")
      (node (ref "U2") (pin "4") (pinfunction "P4_4") (pintype "bidirectional"))
    )
    (net (code "95") (name "unconnected-(USB1-PadNC)") (class "Default")
      (node (ref "USB1") (pin "NC") (pinfunction "NC_NC") (pintype "input"))
    )
  )
)
